# opencryptotoken.net
KiCad netlist of a schematic drawn in EAGLE
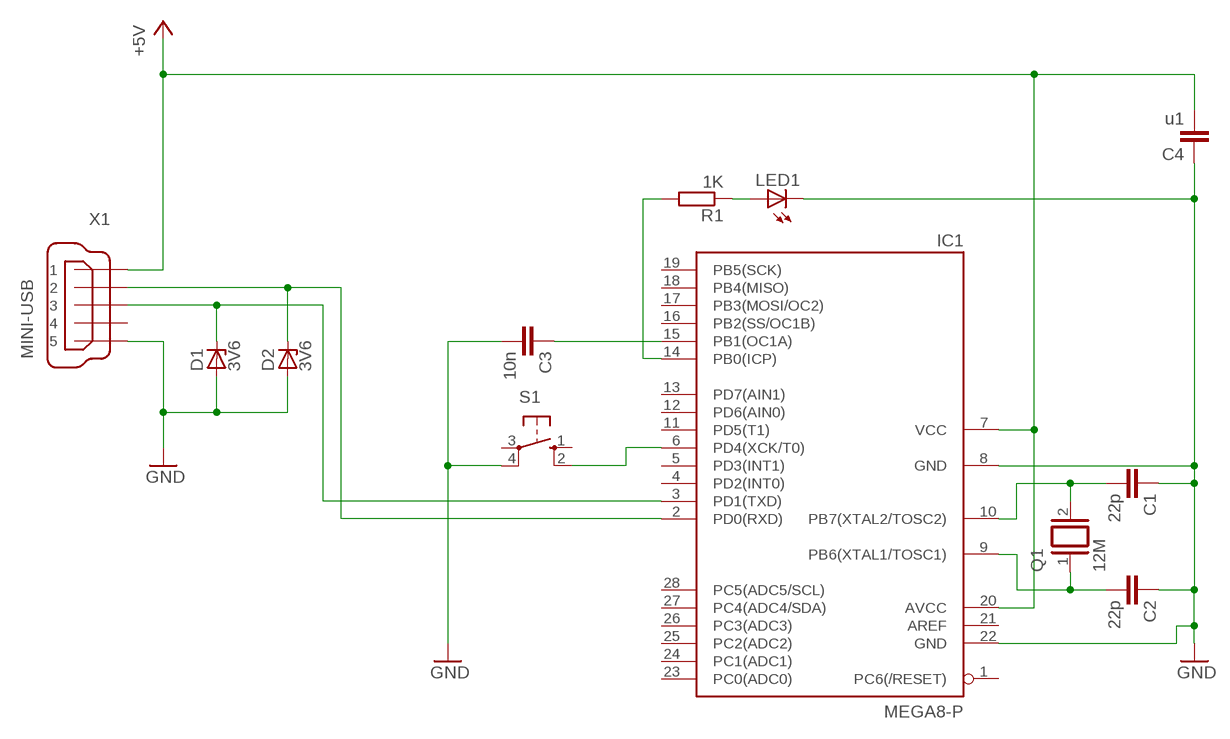
[diagram p0: schematic, sheet 1]

(export (version "E")
  (design (tool "Eeschema 10.0.6"))
  (components
    (comp (ref "C1")
      (value "22p")
      (footprint "eagle-import:C025-024X044")
      (libsource (lib "eagle-import") (part "C-EU025-024X044"))
    )
    (comp (ref "C2")
      (value "22p")
      (footprint "eagle-import:C025-024X044")
      (libsource (lib "eagle-import") (part "C-EU025-024X044"))
    )
    (comp (ref "C3")
      (value "10n")
      (footprint "eagle-import:C025-024X044")
      (libsource (lib "eagle-import") (part "C-EU025-024X044"))
    )
    (comp (ref "C4")
      (value "u1")
      (footprint "eagle-import:C025-024X044")
      (libsource (lib "eagle-import") (part "C-EU025-024X044"))
    )
    (comp (ref "D1")
      (value "3V6")
      (footprint "eagle-import:ZDIO-2.5")
      (libsource (lib "eagle-import") (part "ZENER-DIODEZD-2.5"))
    )
    (comp (ref "D2")
      (value "3V6")
      (footprint "eagle-import:ZDIO-5")
      (libsource (lib "eagle-import") (part "ZENER-DIODEZD-5"))
    )
    (comp (ref "IC1")
      (value "MEGA8-P")
      (footprint "eagle-import:DIL28-3")
      (libsource (lib "eagle-import") (part "MEGA8-P"))
    )
    (comp (ref "LED1")
      (value "LED5MM")
      (footprint "eagle-import:LED5MM")
      (libsource (lib "eagle-import") (part "LED5MM"))
    )
    (comp (ref "Q1")
      (value "12M")
      (footprint "eagle-import:QS")
      (libsource (lib "eagle-import") (part "XTAL/S"))
    )
    (comp (ref "R1")
      (value "1K")
      (footprint "eagle-import:0204V")
      (libsource (lib "eagle-import") (part "R-EU_0204/2V"))
    )
    (comp (ref "S1")
      (value "10-XX")
      (footprint "eagle-import:B3F-10XX")
      (fields (field (name "MPN") "B3F-1000"))
      (libsource (lib "eagle-import") (part "10-XX"))
    )
    (comp (ref "X1")
      (value "MINI-USB")
      (footprint "eagle-import:32005-601")
      (libsource (lib "eagle-import") (part "MINI-USB_SHIELD5P2-32005-601"))
    )
  )
  (nets
    (net (code "1") (name "+5V") (class "Default")
      (node (ref "C4") (pin "2") (pinfunction "2_2") (pintype "passive"))
      (node (ref "IC1") (pin "20") (pinfunction "AVCC_20") (pintype "power_in"))
      (node (ref "IC1") (pin "7") (pinfunction "VCC_7") (pintype "power_in"))
      (node (ref "X1") (pin "1") (pinfunction "1_1") (pintype "passive"))
    )
    (net (code "2") (name "GND") (class "Default")
      (node (ref "C1") (pin "1") (pinfunction "1_1") (pintype "passive"))
      (node (ref "C2") (pin "1") (pinfunction "1_1") (pintype "passive"))
      (node (ref "C3") (pin "2") (pinfunction "2_2") (pintype "passive"))
      (node (ref "C4") (pin "1") (pinfunction "1_1") (pintype "passive"))
      (node (ref "D1") (pin "A") (pinfunction "A_A") (pintype "passive"))
      (node (ref "D2") (pin "A") (pinfunction "A_A") (pintype "passive"))
      (node (ref "IC1") (pin "22") (pinfunction "GND_22") (pintype "power_in"))
      (node (ref "IC1") (pin "8") (pinfunction "GND_8") (pintype "power_in"))
      (node (ref "LED1") (pin "K") (pinfunction "C_K") (pintype "passive"))
      (node (ref "S1") (pin "4") (pinfunction "P1_4") (pintype "passive"))
      (node (ref "X1") (pin "5") (pinfunction "5_5") (pintype "passive"))
    )
    (net (code "3") (name "Net-(IC1-PB0(ICP))") (class "Default")
      (node (ref "IC1") (pin "14") (pinfunction "PB0(ICP)_14") (pintype "bidirectional"))
      (node (ref "R1") (pin "2") (pinfunction "2_2") (pintype "passive"))
    )
    (net (code "4") (name "Net-(IC1-PB1(OC1A))") (class "Default")
      (node (ref "C3") (pin "1") (pinfunction "1_1") (pintype "passive"))
      (node (ref "IC1") (pin "15") (pinfunction "PB1(OC1A)_15") (pintype "bidirectional"))
    )
    (net (code "5") (name "Net-(IC1-PB6(XTAL1{slash}TOSC1))") (class "Default")
      (node (ref "C2") (pin "2") (pinfunction "2_2") (pintype "passive"))
      (node (ref "IC1") (pin "9") (pinfunction "PB6(XTAL1/TOSC1)_9") (pintype "bidirectional"))
      (node (ref "Q1") (pin "1") (pinfunction "1_1") (pintype "passive"))
    )
    (net (code "6") (name "Net-(IC1-PB7(XTAL2{slash}TOSC2))") (class "Default")
      (node (ref "C1") (pin "2") (pinfunction "2_2") (pintype "passive"))
      (node (ref "IC1") (pin "10") (pinfunction "PB7(XTAL2/TOSC2)_10") (pintype "bidirectional"))
      (node (ref "Q1") (pin "2") (pinfunction "2_2") (pintype "passive"))
    )
    (net (code "7") (name "Net-(IC1-PD0(RXD))") (class "Default")
      (node (ref "D2") (pin "C") (pinfunction "C_C") (pintype "passive"))
      (node (ref "IC1") (pin "2") (pinfunction "PD0(RXD)_2") (pintype "bidirectional"))
      (node (ref "X1") (pin "2") (pinfunction "2_2") (pintype "passive"))
    )
    (net (code "8") (name "Net-(IC1-PD1(TXD))") (class "Default")
      (node (ref "D1") (pin "C") (pinfunction "C_C") (pintype "passive"))
      (node (ref "IC1") (pin "3") (pinfunction "PD1(TXD)_3") (pintype "bidirectional"))
      (node (ref "X1") (pin "3") (pinfunction "3_3") (pintype "passive"))
    )
    (net (code "9") (name "Net-(IC1-PD4(XCK{slash}T0))") (class "Default")
      (node (ref "IC1") (pin "6") (pinfunction "PD4(XCK/T0)_6") (pintype "bidirectional"))
      (node (ref "S1") (pin "2") (pinfunction "S1_2") (pintype "passive"))
    )
    (net (code "10") (name "Net-(LED1-PadA)") (class "Default")
      (node (ref "LED1") (pin "A") (pinfunction "A_A") (pintype "passive"))
      (node (ref "R1") (pin "1") (pinfunction "1_1") (pintype "passive"))
    )
    (net (code "11") (name "unconnected-(IC1-AREF-Pad21)") (class "Default")
      (node (ref "IC1") (pin "21") (pinfunction "AREF_21") (pintype "passive"))
    )
    (net (code "12") (name "unconnected-(IC1-PB2(SS{slash}OC1B)-Pad16)") (class "Default")
      (node (ref "IC1") (pin "16") (pinfunction "PB2(SS/OC1B)_16") (pintype "bidirectional"))
    )
    (net (code "13") (name "unconnected-(IC1-PB3(MOSI{slash}OC2)-Pad17)") (class "Default")
      (node (ref "IC1") (pin "17") (pinfunction "PB3(MOSI/OC2)_17") (pintype "bidirectional"))
    )
    (net (code "14") (name "unconnected-(IC1-PB4(MISO)-Pad18)") (class "Default")
      (node (ref "IC1") (pin "18") (pinfunction "PB4(MISO)_18") (pintype "bidirectional"))
    )
    (net (code "15") (name "unconnected-(IC1-PB5(SCK)-Pad19)") (class "Default")
      (node (ref "IC1") (pin "19") (pinfunction "PB5(SCK)_19") (pintype "bidirectional"))
    )
    (net (code "16") (name "unconnected-(IC1-PC0(ADC0)-Pad23)") (class "Default")
      (node (ref "IC1") (pin "23") (pinfunction "PC0(ADC0)_23") (pintype "bidirectional"))
    )
    (net (code "17") (name "unconnected-(IC1-PC1(ADC1)-Pad24)") (class "Default")
      (node (ref "IC1") (pin "24") (pinfunction "PC1(ADC1)_24") (pintype "bidirectional"))
    )
    (net (code "18") (name "unconnected-(IC1-PC2(ADC2)-Pad25)") (class "Default")
      (node (ref "IC1") (pin "25") (pinfunction "PC2(ADC2)_25") (pintype "bidirectional"))
    )
    (net (code "19") (name "unconnected-(IC1-PC3(ADC3)-Pad26)") (class "Default")
      (node (ref "IC1") (pin "26") (pinfunction "PC3(ADC3)_26") (pintype "bidirectional"))
    )
    (net (code "20") (name "unconnected-(IC1-PC4(ADC4{slash}SDA)-Pad27)") (class "Default")
      (node (ref "IC1") (pin "27") (pinfunction "PC4(ADC4/SDA)_27") (pintype "bidirectional"))
    )
    (net (code "21") (name "unconnected-(IC1-PC5(ADC5{slash}SCL)-Pad28)") (class "Default")
      (node (ref "IC1") (pin "28") (pinfunction "PC5(ADC5/SCL)_28") (pintype "bidirectional"))
    )
    (net (code "22") (name "unconnected-(IC1-PC6({slash}RESET)-Pad1)") (class "Default")
      (node (ref "IC1") (pin "1") (pinfunction "PC6(/RESET)_1") (pintype "bidirectional"))
    )
    (net (code "23") (name "unconnected-(IC1-PD2(INT0)-Pad4)") (class "Default")
      (node (ref "IC1") (pin "4") (pinfunction "PD2(INT0)_4") (pintype "bidirectional"))
    )
    (net (code "24") (name "unconnected-(IC1-PD3(INT1)-Pad5)") (class "Default")
      (node (ref "IC1") (pin "5") (pinfunction "PD3(INT1)_5") (pintype "bidirectional"))
    )
    (net (code "25") (name "unconnected-(IC1-PD5(T1)-Pad11)") (class "Default")
      (node (ref "IC1") (pin "11") (pinfunction "PD5(T1)_11") (pintype "bidirectional"))
    )
    (net (code "26") (name "unconnected-(IC1-PD6(AIN0)-Pad12)") (class "Default")
      (node (ref "IC1") (pin "12") (pinfunction "PD6(AIN0)_12") (pintype "bidirectional"))
    )
    (net (code "27") (name "unconnected-(IC1-PD7(AIN1)-Pad13)") (class "Default")
      (node (ref "IC1") (pin "13") (pinfunction "PD7(AIN1)_13") (pintype "bidirectional"))
    )
    (net (code "28") (name "unconnected-(S1-P-Pad3)") (class "Default")
      (node (ref "S1") (pin "3") (pinfunction "P_3") (pintype "passive"))
    )
    (net (code "29") (name "unconnected-(S1-S-Pad1)") (class "Default")
      (node (ref "S1") (pin "1") (pinfunction "S_1") (pintype "passive"))
    )
    (net (code "30") (name "unconnected-(X1-Pad4)") (class "Default")
      (node (ref "X1") (pin "4") (pinfunction "4_4") (pintype "passive"))
    )
  )
)
